# Motor.net
KiCad netlist of a schematic drawn in EAGLE
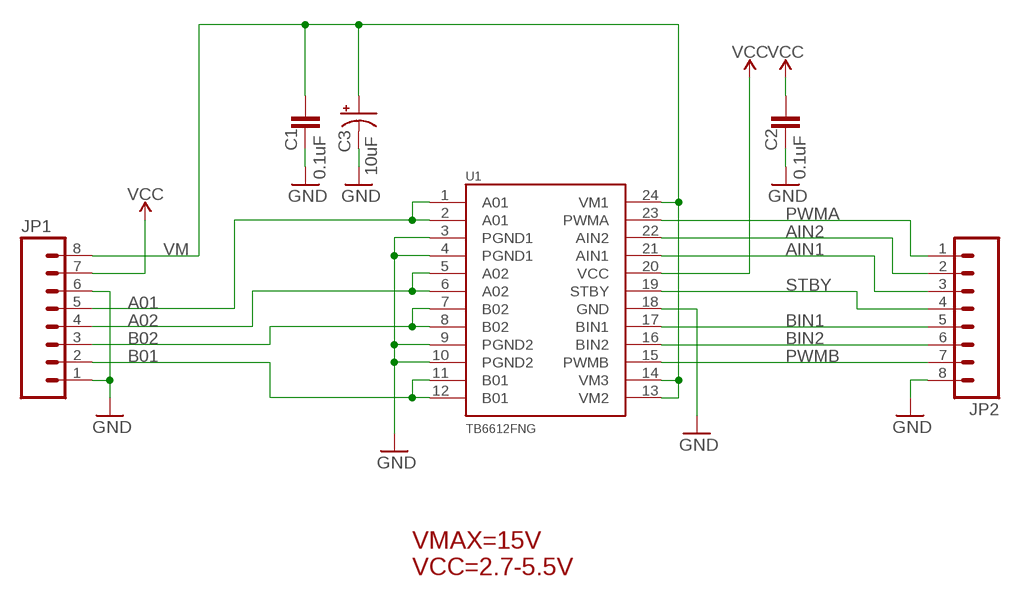
[diagram p0: schematic, sheet 1]

(export (version "E")
  (design (tool "Eeschema 10.0.6"))
  (components
    (comp (ref "C1")
      (value "0.1uF")
      (footprint "eagle-import:0402")
      (libsource (lib "eagle-import") (part "0.1UF-0402-16V-10%"))
    )
    (comp (ref "C2")
      (value "0.1uF")
      (footprint "eagle-import:0402")
      (libsource (lib "eagle-import") (part "0.1UF-0402-16V-10%"))
    )
    (comp (ref "C3")
      (value "10uF")
      (footprint "eagle-import:EIA3528")
      (libsource (lib "eagle-import") (part "10UF-POLAR-EIA3528-20V-10%(TANT)"))
    )
    (comp (ref "JP1")
      (value "M0875_PERCENT_REDUCED")
      (footprint "eagle-import:1X08_OFFSET_REDUCED")
      (libsource (lib "eagle-import") (part "M0875_PERCENT_REDUCED"))
    )
    (comp (ref "JP2")
      (value "M0875_PERCENT_REDUCED")
      (footprint "eagle-import:1X08_OFFSET_REDUCED")
      (libsource (lib "eagle-import") (part "M0875_PERCENT_REDUCED"))
    )
    (comp (ref "U1")
      (value "TB6612FNG")
      (footprint "eagle-import:SSOP24")
      (libsource (lib "eagle-import") (part "TB6612FNG"))
    )
  )
  (nets
    (net (code "1") (name "/A01") (class "Default")
      (node (ref "JP1") (pin "5") (pinfunction "5_5") (pintype "passive"))
      (node (ref "U1") (pin "1") (pinfunction "A01_1") (pintype "bidirectional"))
      (node (ref "U1") (pin "2") (pinfunction "A01_2") (pintype "bidirectional"))
    )
    (net (code "2") (name "/A02") (class "Default")
      (node (ref "JP1") (pin "4") (pinfunction "4_4") (pintype "passive"))
      (node (ref "U1") (pin "5") (pinfunction "A02_5") (pintype "bidirectional"))
      (node (ref "U1") (pin "6") (pinfunction "A02_6") (pintype "bidirectional"))
    )
    (net (code "3") (name "/AIN1") (class "Default")
      (node (ref "JP2") (pin "3") (pinfunction "3_3") (pintype "passive"))
      (node (ref "U1") (pin "21") (pinfunction "AIN1_21") (pintype "bidirectional"))
    )
    (net (code "4") (name "/AIN2") (class "Default")
      (node (ref "JP2") (pin "2") (pinfunction "2_2") (pintype "passive"))
      (node (ref "U1") (pin "22") (pinfunction "AIN2_22") (pintype "bidirectional"))
    )
    (net (code "5") (name "/B01") (class "Default")
      (node (ref "JP1") (pin "2") (pinfunction "2_2") (pintype "passive"))
      (node (ref "U1") (pin "11") (pinfunction "B01_11") (pintype "bidirectional"))
      (node (ref "U1") (pin "12") (pinfunction "B01_12") (pintype "bidirectional"))
    )
    (net (code "6") (name "/B02") (class "Default")
      (node (ref "JP1") (pin "3") (pinfunction "3_3") (pintype "passive"))
      (node (ref "U1") (pin "7") (pinfunction "B02_7") (pintype "bidirectional"))
      (node (ref "U1") (pin "8") (pinfunction "B02_8") (pintype "bidirectional"))
    )
    (net (code "7") (name "/BIN1") (class "Default")
      (node (ref "JP2") (pin "5") (pinfunction "5_5") (pintype "passive"))
      (node (ref "U1") (pin "17") (pinfunction "BIN1_17") (pintype "bidirectional"))
    )
    (net (code "8") (name "/BIN2") (class "Default")
      (node (ref "JP2") (pin "6") (pinfunction "6_6") (pintype "passive"))
      (node (ref "U1") (pin "16") (pinfunction "BIN2_16") (pintype "bidirectional"))
    )
    (net (code "9") (name "/PWMA") (class "Default")
      (node (ref "JP2") (pin "1") (pinfunction "1_1") (pintype "passive"))
      (node (ref "U1") (pin "23") (pinfunction "PWMA_23") (pintype "bidirectional"))
    )
    (net (code "10") (name "/PWMB") (class "Default")
      (node (ref "JP2") (pin "7") (pinfunction "7_7") (pintype "passive"))
      (node (ref "U1") (pin "15") (pinfunction "PWMB_15") (pintype "bidirectional"))
    )
    (net (code "11") (name "/STBY") (class "Default")
      (node (ref "JP2") (pin "4") (pinfunction "4_4") (pintype "passive"))
      (node (ref "U1") (pin "19") (pinfunction "STBY_19") (pintype "bidirectional"))
    )
    (net (code "12") (name "/VM") (class "Default")
      (node (ref "C1") (pin "1") (pinfunction "1_1") (pintype "passive"))
      (node (ref "C3") (pin "A") (pinfunction "+_A") (pintype "passive"))
      (node (ref "JP1") (pin "8") (pinfunction "8_8") (pintype "passive"))
      (node (ref "U1") (pin "13") (pinfunction "VM2_13") (pintype "bidirectional"))
      (node (ref "U1") (pin "14") (pinfunction "VM3_14") (pintype "bidirectional"))
      (node (ref "U1") (pin "24") (pinfunction "VM1_24") (pintype "bidirectional"))
    )
    (net (code "13") (name "GND") (class "Default")
      (node (ref "C1") (pin "2") (pinfunction "2_2") (pintype "passive"))
      (node (ref "C2") (pin "2") (pinfunction "2_2") (pintype "passive"))
      (node (ref "C3") (pin "C") (pinfunction "-_C") (pintype "passive"))
      (node (ref "JP1") (pin "1") (pinfunction "1_1") (pintype "passive"))
      (node (ref "JP1") (pin "6") (pinfunction "6_6") (pintype "passive"))
      (node (ref "JP2") (pin "8") (pinfunction "8_8") (pintype "passive"))
      (node (ref "U1") (pin "10") (pinfunction "PGND2_10") (pintype "bidirectional"))
      (node (ref "U1") (pin "18") (pinfunction "GND_18") (pintype "bidirectional"))
      (node (ref "U1") (pin "3") (pinfunction "PGND1_3") (pintype "bidirectional"))
      (node (ref "U1") (pin "4") (pinfunction "PGND1_4") (pintype "bidirectional"))
      (node (ref "U1") (pin "9") (pinfunction "PGND2_9") (pintype "bidirectional"))
    )
    (net (code "14") (name "VCC") (class "Default")
      (node (ref "C2") (pin "1") (pinfunction "1_1") (pintype "passive"))
      (node (ref "JP1") (pin "7") (pinfunction "7_7") (pintype "passive"))
      (node (ref "U1") (pin "20") (pinfunction "VCC_20") (pintype "bidirectional"))
    )
  )
)
